# ProDoc_V2_0__2025-08-21.net
KiCad netlist of a schematic drawn in EasyEDA Pro
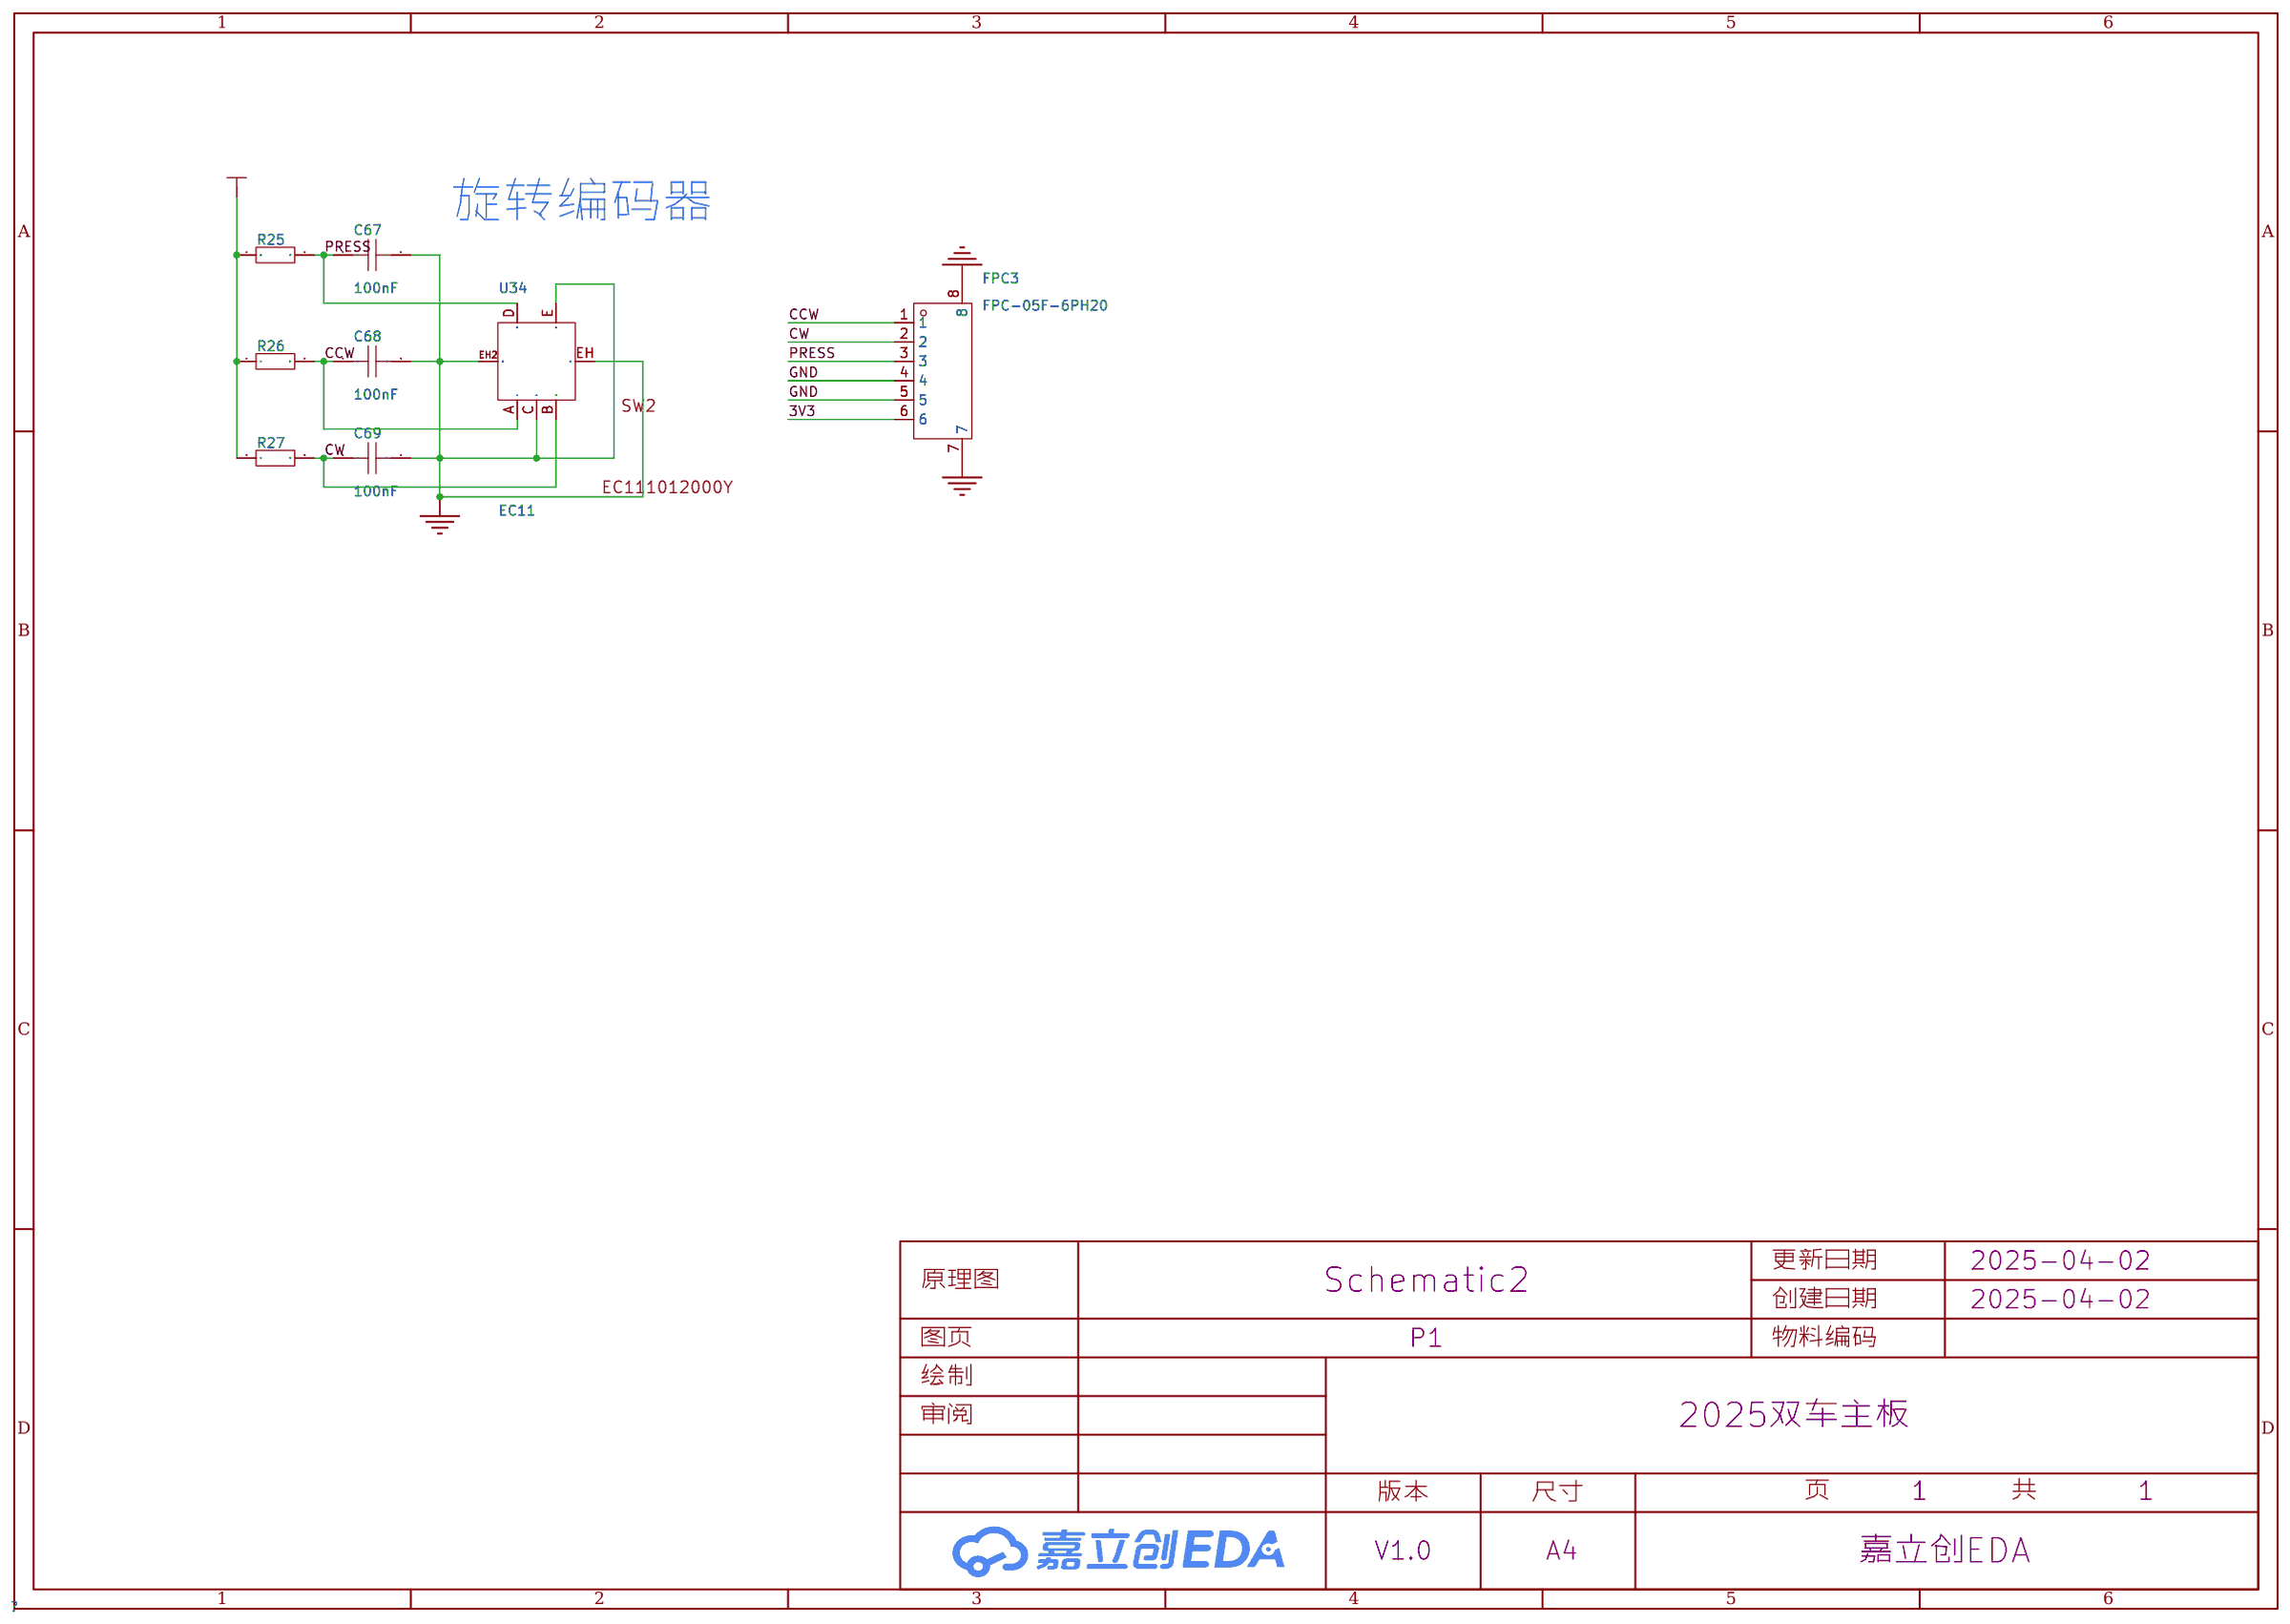
[diagram p0: schematic sheet]

(export (version "E")
  (design (tool "Eeschema 10.0.6"))
  (components
    (comp (ref "C67")
      (value "100nF")
      (footprint "easyedapro:C0603")
      (description "容值:100nF;精度:±10%;额定电压:50V;材质(温度系数):X7R;")
      (fields
        (field (name "Manufacturer Part") "CGA0603X7R104K500JT")
        (field (name "Manufacturer") "HRE(芯声)")
      )
      (libsource (lib "easyedapro") (part "CGA0603X7R104K500JT"))
    )
    (comp (ref "C68")
      (value "100nF")
      (footprint "easyedapro:C0603")
      (description "容值:100nF;精度:±10%;额定电压:50V;材质(温度系数):X7R;")
      (fields
        (field (name "Manufacturer Part") "CGA0603X7R104K500JT")
        (field (name "Manufacturer") "HRE(芯声)")
      )
      (libsource (lib "easyedapro") (part "CGA0603X7R104K500JT"))
    )
    (comp (ref "C69")
      (value "100nF")
      (footprint "easyedapro:C0603")
      (description "容值:100nF;精度:±10%;额定电压:50V;材质(温度系数):X7R;")
      (fields
        (field (name "Manufacturer Part") "CGA0603X7R104K500JT")
        (field (name "Manufacturer") "HRE(芯声)")
      )
      (libsource (lib "easyedapro") (part "CGA0603X7R104K500JT"))
    )
    (comp (ref "FPC3")
      (value "FPC-05F-6PH20")
      (footprint "easyedapro:FPC-SMD_6P-P0.50_XUNPU_FPC-05F-6PH20")
      (description "锁定特性:翻盖式;触点类型:下接;触点数量:6P;间距:0.5mm;安装类型:卧贴;工作温度范围:-25°C~+85°C;")
      (fields (field (name "Manufacturer") "XUNPU(讯普)"))
      (libsource (lib "easyedapro") (part "FPC-05F-6PH20"))
    )
    (comp (ref "R25") (value "10kΩ") (libsource (lib "easyedapro") (part "0603WAF1002T5E")))
    (comp (ref "R26") (value "10kΩ") (libsource (lib "easyedapro") (part "0603WAF1002T5E")))
    (comp (ref "R27") (value "10kΩ") (libsource (lib "easyedapro") (part "0603WAF1002T5E")))
    (comp (ref "U34")
      (value "EC11")
      (footprint "easyedapro:EC11卧式")
      (libsource (lib "easyedapro") (part "EC11"))
    )
  )
  (nets
    (net (code "1") (name "/CCW") (class "Default")
      (node (ref "C68") (pin "1") (pinfunction "1_1") (pintype "unspecified"))
      (node (ref "FPC3") (pin "1") (pinfunction "1_1") (pintype "unspecified"))
      (node (ref "R26") (pin "2") (pinfunction "2_2") (pintype "input"))
      (node (ref "U34") (pin "A") (pinfunction "A_A") (pintype "unspecified"))
    )
    (net (code "2") (name "/CW") (class "Default")
      (node (ref "C69") (pin "2") (pinfunction "2_2") (pintype "unspecified"))
      (node (ref "FPC3") (pin "2") (pinfunction "2_2") (pintype "unspecified"))
      (node (ref "R27") (pin "2") (pinfunction "2_2") (pintype "input"))
      (node (ref "U34") (pin "B") (pinfunction "B_B") (pintype "unspecified"))
    )
    (net (code "3") (name "/PRESS") (class "Default")
      (node (ref "C67") (pin "1") (pinfunction "1_1") (pintype "unspecified"))
      (node (ref "FPC3") (pin "3") (pinfunction "3_3") (pintype "unspecified"))
      (node (ref "R25") (pin "2") (pinfunction "2_2") (pintype "input"))
      (node (ref "U34") (pin "D") (pinfunction "D_D") (pintype "unspecified"))
    )
    (net (code "4") (name "3V3") (class "Default")
      (node (ref "FPC3") (pin "6") (pinfunction "6_6") (pintype "unspecified"))
      (node (ref "R25") (pin "1") (pinfunction "1_1") (pintype "input"))
      (node (ref "R26") (pin "1") (pinfunction "1_1") (pintype "input"))
      (node (ref "R27") (pin "1") (pinfunction "1_1") (pintype "input"))
    )
    (net (code "5") (name "GND") (class "Default")
      (node (ref "C67") (pin "2") (pinfunction "2_2") (pintype "unspecified"))
      (node (ref "C68") (pin "2") (pinfunction "2_2") (pintype "unspecified"))
      (node (ref "C69") (pin "1") (pinfunction "1_1") (pintype "unspecified"))
      (node (ref "FPC3") (pin "4") (pinfunction "4_4") (pintype "unspecified"))
      (node (ref "FPC3") (pin "5") (pinfunction "5_5") (pintype "unspecified"))
      (node (ref "FPC3") (pin "7") (pinfunction "7_7") (pintype "unspecified"))
      (node (ref "FPC3") (pin "8") (pinfunction "8_8") (pintype "unspecified"))
      (node (ref "U34") (pin "C") (pinfunction "C_C") (pintype "unspecified"))
      (node (ref "U34") (pin "E") (pinfunction "E_E") (pintype "unspecified"))
      (node (ref "U34") (pin "EH") (pinfunction "EH_EH") (pintype "unspecified"))
      (node (ref "U34") (pin "EH2") (pinfunction "EH2_EH2") (pintype "unspecified"))
    )
  )
)
